# design.net
KiCad netlist of a schematic drawn in Altium Designer
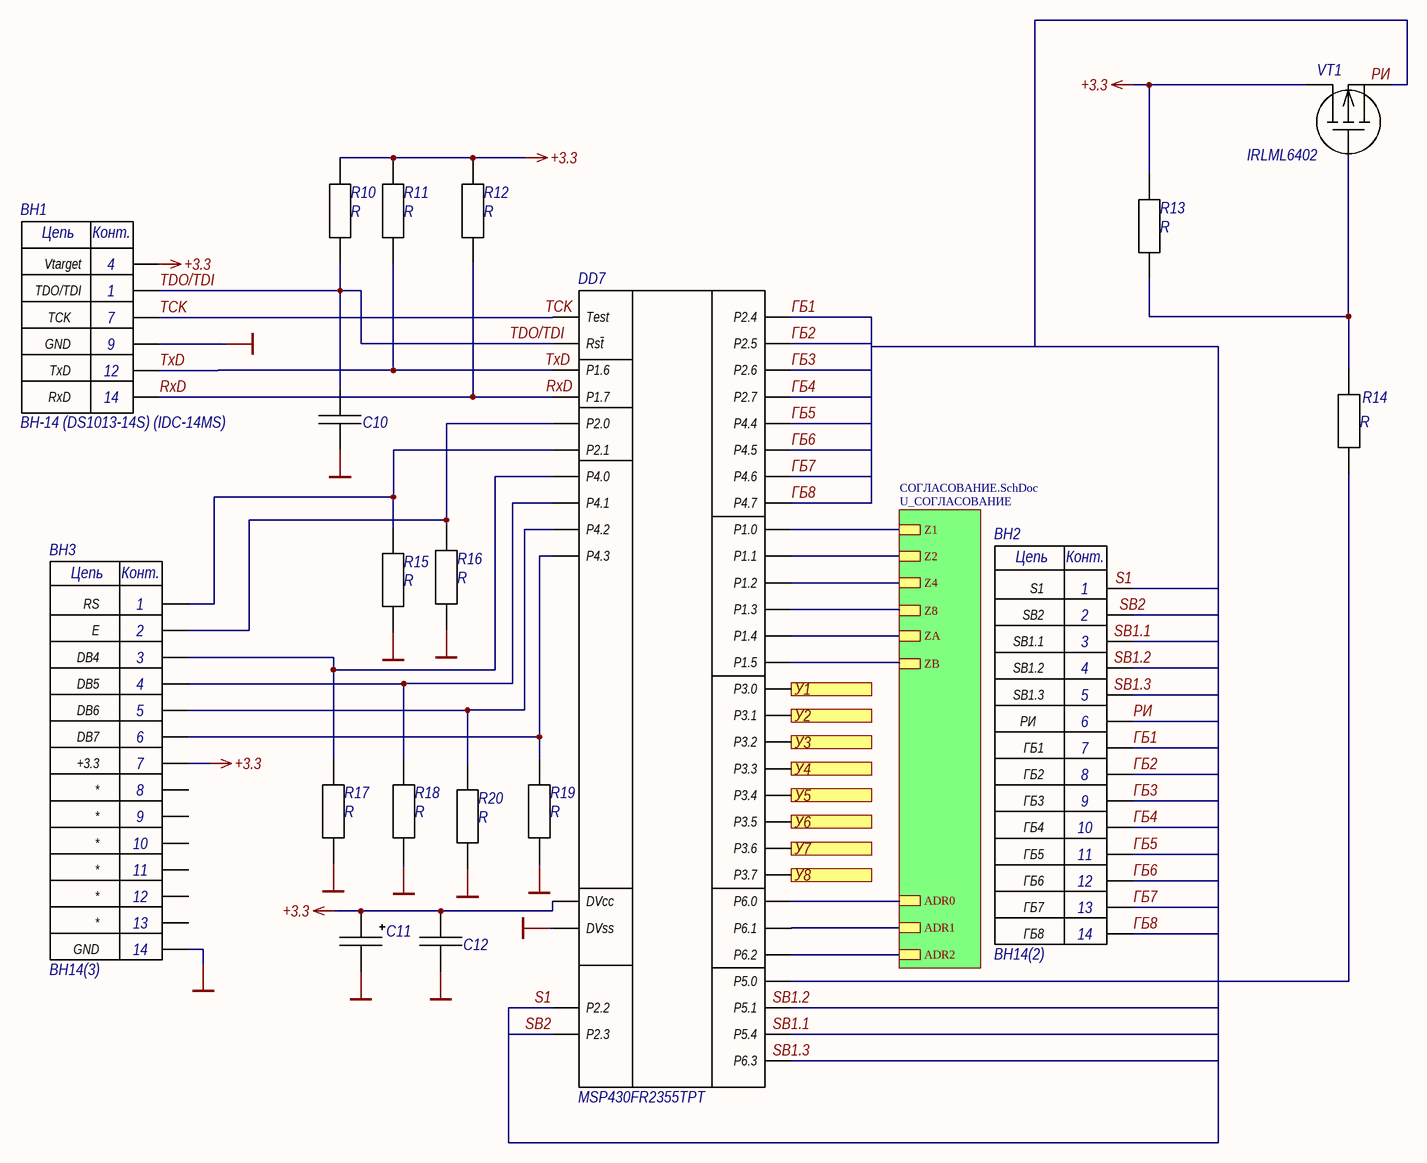
[diagram p0: УПРАВЛ.SchDoc]

(export (version "E")
  (design (tool "Eeschema 10.0.6"))
  (components
    (comp (ref "BH1")
      (value "BH-14 (DS1013-14S) (IDC-14MS)")
      (footprint "BH-14 (DS1013-14S) (IDC-14MS)")
      (libsource (lib "UGO") (part "BH-14 (DS1013-14S) (IDC-14MS)"))
    )
    (comp (ref "BH2")
      (value "BH14(2)")
      (footprint "BH-14 (DS1013-14S) (IDC-14MS)")
      (libsource (lib "UGO") (part "BH14(2)"))
    )
    (comp (ref "BH3")
      (value "BH14(3)")
      (footprint "BH-14 (DS1013-14S) (IDC-14MS)")
      (libsource (lib "UGO") (part "BH14(3)"))
    )
    (comp (ref "C10")
      (value "C(ceramic)")
      (footprint "C(ceramic)")
      (libsource (lib "UGO") (part "C(ceramic)"))
    )
    (comp (ref "C11") (value "C(AlEL)") (footprint "C(AlEL)") (libsource (lib "UGO") (part "C(AlEL)")))
    (comp (ref "C12")
      (value "C(ceramic)")
      (footprint "C(ceramic)")
      (libsource (lib "UGO") (part "C(ceramic)"))
    )
    (comp (ref "DD7")
      (value "MSP430FR2355TPT")
      (footprint "MSP430FR2355TPT")
      (libsource (lib "UGO") (part "MSP430FR2355TPT"))
    )
    (comp (ref "R10") (value "R") (footprint "R") (libsource (lib "UGO") (part "R")))
    (comp (ref "R11") (value "R") (footprint "R") (libsource (lib "UGO") (part "R")))
    (comp (ref "R12") (value "R") (footprint "R") (libsource (lib "UGO") (part "R")))
    (comp (ref "R13") (value "R") (footprint "R") (libsource (lib "UGO") (part "R")))
    (comp (ref "R14") (value "R") (footprint "R") (libsource (lib "UGO") (part "R")))
    (comp (ref "R15") (value "R") (footprint "R") (libsource (lib "UGO") (part "R")))
    (comp (ref "R16") (value "R") (footprint "R") (libsource (lib "UGO") (part "R")))
    (comp (ref "R17") (value "R") (footprint "R") (libsource (lib "UGO") (part "R")))
    (comp (ref "R18") (value "R") (footprint "R") (libsource (lib "UGO") (part "R")))
    (comp (ref "R19") (value "R") (footprint "R") (libsource (lib "UGO") (part "R")))
    (comp (ref "R20") (value "R") (footprint "R") (libsource (lib "UGO") (part "R")))
    (comp (ref "VT1")
      (value "IRLML6402")
      (footprint "BC847(IRLML6402)")
      (libsource (lib "UGO") (part "IRLML6402"))
    )
  )
  (nets
    (net (code "1") (name "+3.3") (class "Default")
      (node (ref "BH1") (pin "4") (pinfunction "Vtarget_4") (pintype "passive"))
      (node (ref "BH3") (pin "7") (pinfunction "+3.3_7") (pintype "passive"))
      (node (ref "C11") (pin "1") (pintype "passive"))
      (node (ref "C12") (pin "2") (pintype "passive"))
      (node (ref "DD7") (pin "6") (pinfunction "DVcc_6") (pintype "passive"))
      (node (ref "R10") (pin "2") (pintype "passive"))
      (node (ref "R11") (pin "2") (pintype "passive"))
      (node (ref "R12") (pin "2") (pintype "passive"))
      (node (ref "R13") (pin "2") (pintype "passive"))
      (node (ref "VT1") (pin "3") (pintype "passive"))
    )
    (net (code "2") (name "/ADR0") (class "Default")
      (node (ref "DD7") (pin "22") (pinfunction "P6.0_22") (pintype "passive"))
    )
    (net (code "3") (name "/ADR1") (class "Default")
      (node (ref "DD7") (pin "21") (pinfunction "P6.1_21") (pintype "passive"))
    )
    (net (code "4") (name "/ADR2") (class "Default")
      (node (ref "DD7") (pin "20") (pinfunction "P6.2_20") (pintype "passive"))
    )
    (net (code "5") (name "/RxD") (class "Default")
      (node (ref "BH1") (pin "14") (pinfunction "RxD_14") (pintype "passive"))
      (node (ref "DD7") (pin "31") (pinfunction "P1.7_31") (pintype "passive"))
      (node (ref "R12") (pin "1") (pintype "passive"))
    )
    (net (code "6") (name "/S1") (class "Default")
      (node (ref "BH2") (pin "1") (pinfunction "S1_1") (pintype "passive"))
      (node (ref "DD7") (pin "28") (pinfunction "P2.2_28") (pintype "passive"))
    )
    (net (code "7") (name "/SB1.1") (class "Default")
      (node (ref "BH2") (pin "3") (pinfunction "SB1.1_3") (pintype "passive"))
      (node (ref "DD7") (pin "39") (pinfunction "P5.4_39") (pintype "passive"))
    )
    (net (code "8") (name "/SB1.2") (class "Default")
      (node (ref "BH2") (pin "4") (pinfunction "SB1.2_4") (pintype "passive"))
      (node (ref "DD7") (pin "42") (pinfunction "P5.1_42") (pintype "passive"))
    )
    (net (code "9") (name "/SB1.3") (class "Default")
      (node (ref "BH2") (pin "5") (pinfunction "SB1.3_5") (pintype "passive"))
      (node (ref "DD7") (pin "19") (pinfunction "P6.3_19") (pintype "passive"))
    )
    (net (code "10") (name "/SB2") (class "Default")
      (node (ref "BH2") (pin "2") (pinfunction "SB2_2") (pintype "passive"))
      (node (ref "DD7") (pin "27") (pinfunction "P2.3_27") (pintype "passive"))
    )
    (net (code "11") (name "/TCK") (class "Default")
      (node (ref "BH1") (pin "7") (pinfunction "TCK_7") (pintype "passive"))
      (node (ref "DD7") (pin "4") (pinfunction "Test_4") (pintype "passive"))
    )
    (net (code "12") (name "/TDO{slash}TDI") (class "Default")
      (node (ref "BH1") (pin "1") (pinfunction "TDO/TDI_1") (pintype "passive"))
      (node (ref "C10") (pin "2") (pintype "passive"))
      (node (ref "DD7") (pin "5") (pinfunction "Rs~{t}_5") (pintype "passive"))
      (node (ref "R10") (pin "1") (pintype "passive"))
    )
    (net (code "13") (name "/TxD") (class "Default")
      (node (ref "BH1") (pin "12") (pinfunction "TxD_12") (pintype "passive"))
      (node (ref "DD7") (pin "32") (pinfunction "P1.6_32") (pintype "passive"))
      (node (ref "R11") (pin "1") (pintype "passive"))
    )
    (net (code "14") (name "/Z1") (class "Default")
      (node (ref "DD7") (pin "3") (pinfunction "P1.0_3") (pintype "passive"))
    )
    (net (code "15") (name "/Z2") (class "Default")
      (node (ref "DD7") (pin "2") (pinfunction "P1.1_2") (pintype "passive"))
    )
    (net (code "16") (name "/Z4") (class "Default")
      (node (ref "DD7") (pin "1") (pinfunction "P1.2_1") (pintype "passive"))
    )
    (net (code "17") (name "/Z8") (class "Default")
      (node (ref "DD7") (pin "48") (pinfunction "P1.3_48") (pintype "passive"))
    )
    (net (code "18") (name "/ZA") (class "Default")
      (node (ref "DD7") (pin "34") (pinfunction "P1.4_34") (pintype "passive"))
    )
    (net (code "19") (name "/ZB") (class "Default")
      (node (ref "DD7") (pin "33") (pinfunction "P1.5_33") (pintype "passive"))
    )
    (net (code "20") (name "/ГБ1") (class "Default")
      (node (ref "BH2") (pin "7") (pinfunction "ГБ1_7") (pintype "passive"))
      (node (ref "DD7") (pin "11") (pinfunction "P2.4_11") (pintype "passive"))
    )
    (net (code "21") (name "/ГБ2") (class "Default")
      (node (ref "BH2") (pin "8") (pinfunction "ГБ2_8") (pintype "passive"))
      (node (ref "DD7") (pin "10") (pinfunction "P2.5_10") (pintype "passive"))
    )
    (net (code "22") (name "/ГБ3") (class "Default")
      (node (ref "BH2") (pin "9") (pinfunction "ГБ3_9") (pintype "passive"))
      (node (ref "DD7") (pin "9") (pinfunction "P2.6_9") (pintype "passive"))
    )
    (net (code "23") (name "/ГБ4") (class "Default")
      (node (ref "BH2") (pin "10") (pinfunction "ГБ4_10") (pintype "passive"))
      (node (ref "DD7") (pin "8") (pinfunction "P2.7_8") (pintype "passive"))
    )
    (net (code "24") (name "/ГБ5") (class "Default")
      (node (ref "BH2") (pin "11") (pinfunction "ГБ5_11") (pintype "passive"))
      (node (ref "DD7") (pin "15") (pinfunction "P4.4_15") (pintype "passive"))
    )
    (net (code "25") (name "/ГБ6") (class "Default")
      (node (ref "BH2") (pin "12") (pinfunction "ГБ6_12") (pintype "passive"))
      (node (ref "DD7") (pin "14") (pinfunction "P4.5_14") (pintype "passive"))
    )
    (net (code "26") (name "/ГБ7") (class "Default")
      (node (ref "BH2") (pin "13") (pinfunction "ГБ7_13") (pintype "passive"))
      (node (ref "DD7") (pin "13") (pinfunction "P4.6_13") (pintype "passive"))
    )
    (net (code "27") (name "/ГБ8") (class "Default")
      (node (ref "BH2") (pin "14") (pinfunction "ГБ8_14") (pintype "passive"))
      (node (ref "DD7") (pin "12") (pinfunction "P4.7_12") (pintype "passive"))
    )
    (net (code "28") (name "/РИ") (class "Default")
      (node (ref "BH2") (pin "6") (pinfunction "РИ_6") (pintype "passive"))
      (node (ref "VT1") (pin "2") (pintype "passive"))
    )
    (net (code "29") (name "/У1") (class "Default")
      (node (ref "DD7") (pin "47") (pinfunction "P3.0_47") (pintype "passive"))
    )
    (net (code "30") (name "/У2") (class "Default")
      (node (ref "DD7") (pin "46") (pinfunction "P3.1_46") (pintype "passive"))
    )
    (net (code "31") (name "/У3") (class "Default")
      (node (ref "DD7") (pin "45") (pinfunction "P3.2_45") (pintype "passive"))
    )
    (net (code "32") (name "/У4") (class "Default")
      (node (ref "DD7") (pin "44") (pinfunction "P3.3_44") (pintype "passive"))
    )
    (net (code "33") (name "/У5") (class "Default")
      (node (ref "DD7") (pin "38") (pinfunction "P3.4_38") (pintype "passive"))
    )
    (net (code "34") (name "/У6") (class "Default")
      (node (ref "DD7") (pin "37") (pinfunction "P3.5_37") (pintype "passive"))
    )
    (net (code "35") (name "/У7") (class "Default")
      (node (ref "DD7") (pin "36") (pinfunction "P3.6_36") (pintype "passive"))
    )
    (net (code "36") (name "/У8") (class "Default")
      (node (ref "DD7") (pin "35") (pinfunction "P3.7_35") (pintype "passive"))
    )
    (net (code "37") (name "GND") (class "Default")
      (node (ref "BH1") (pin "9") (pinfunction "GND_9") (pintype "passive"))
      (node (ref "BH3") (pin "14") (pinfunction "GND_14") (pintype "passive"))
      (node (ref "C10") (pin "1") (pintype "passive"))
      (node (ref "C11") (pin "2") (pintype "passive"))
      (node (ref "C12") (pin "1") (pintype "passive"))
      (node (ref "DD7") (pin "7") (pinfunction "DVss_7") (pintype "passive"))
      (node (ref "R15") (pin "1") (pintype "passive"))
      (node (ref "R16") (pin "1") (pintype "passive"))
      (node (ref "R17") (pin "1") (pintype "passive"))
      (node (ref "R18") (pin "1") (pintype "passive"))
      (node (ref "R19") (pin "1") (pintype "passive"))
      (node (ref "R20") (pin "1") (pintype "passive"))
    )
    (net (code "38") (name "Net-(BH3-DB4)") (class "Default")
      (node (ref "BH3") (pin "3") (pinfunction "DB4_3") (pintype "passive"))
      (node (ref "DD7") (pin "26") (pinfunction "P4.0_26") (pintype "passive"))
      (node (ref "R17") (pin "2") (pintype "passive"))
    )
    (net (code "39") (name "Net-(BH3-DB5)") (class "Default")
      (node (ref "BH3") (pin "4") (pinfunction "DB5_4") (pintype "passive"))
      (node (ref "DD7") (pin "25") (pinfunction "P4.1_25") (pintype "passive"))
      (node (ref "R18") (pin "2") (pintype "passive"))
    )
    (net (code "40") (name "Net-(BH3-DB6)") (class "Default")
      (node (ref "BH3") (pin "5") (pinfunction "DB6_5") (pintype "passive"))
      (node (ref "DD7") (pin "24") (pinfunction "P4.2_24") (pintype "passive"))
      (node (ref "R20") (pin "2") (pintype "passive"))
    )
    (net (code "41") (name "Net-(BH3-DB7)") (class "Default")
      (node (ref "BH3") (pin "6") (pinfunction "DB7_6") (pintype "passive"))
      (node (ref "DD7") (pin "23") (pinfunction "P4.3_23") (pintype "passive"))
      (node (ref "R19") (pin "2") (pintype "passive"))
    )
    (net (code "42") (name "Net-(BH3-E)") (class "Default")
      (node (ref "BH3") (pin "2") (pinfunction "E_2") (pintype "passive"))
      (node (ref "DD7") (pin "30") (pinfunction "P2.0_30") (pintype "passive"))
      (node (ref "R16") (pin "2") (pintype "passive"))
    )
    (net (code "43") (name "Net-(BH3-RS)") (class "Default")
      (node (ref "BH3") (pin "1") (pinfunction "RS_1") (pintype "passive"))
      (node (ref "DD7") (pin "29") (pinfunction "P2.1_29") (pintype "passive"))
      (node (ref "R15") (pin "2") (pintype "passive"))
    )
    (net (code "44") (name "Net-(DD7-P5.0)") (class "Default")
      (node (ref "DD7") (pin "43") (pinfunction "P5.0_43") (pintype "passive"))
      (node (ref "R14") (pin "1") (pintype "passive"))
    )
    (net (code "45") (name "Net-(R13-Pad1)") (class "Default")
      (node (ref "R13") (pin "1") (pintype "passive"))
      (node (ref "R14") (pin "2") (pintype "passive"))
      (node (ref "VT1") (pin "1") (pintype "passive"))
    )
    (net (code "46") (name "unconnected-(BH3-*-Pad8)") (class "Default")
      (node (ref "BH3") (pin "8") (pinfunction "*_8") (pintype "passive"))
    )
    (net (code "47") (name "unconnected-(BH3-*-Pad9)") (class "Default")
      (node (ref "BH3") (pin "9") (pinfunction "*_9") (pintype "passive"))
    )
    (net (code "48") (name "unconnected-(BH3-*-Pad10)") (class "Default")
      (node (ref "BH3") (pin "10") (pinfunction "*_10") (pintype "passive"))
    )
    (net (code "49") (name "unconnected-(BH3-*-Pad11)") (class "Default")
      (node (ref "BH3") (pin "11") (pinfunction "*_11") (pintype "passive"))
    )
    (net (code "50") (name "unconnected-(BH3-*-Pad12)") (class "Default")
      (node (ref "BH3") (pin "12") (pinfunction "*_12") (pintype "passive"))
    )
    (net (code "51") (name "unconnected-(BH3-*-Pad13)") (class "Default")
      (node (ref "BH3") (pin "13") (pinfunction "*_13") (pintype "passive"))
    )
  )
)
